# Schematic.net
KiCad netlist of a schematic drawn in Altium Designer
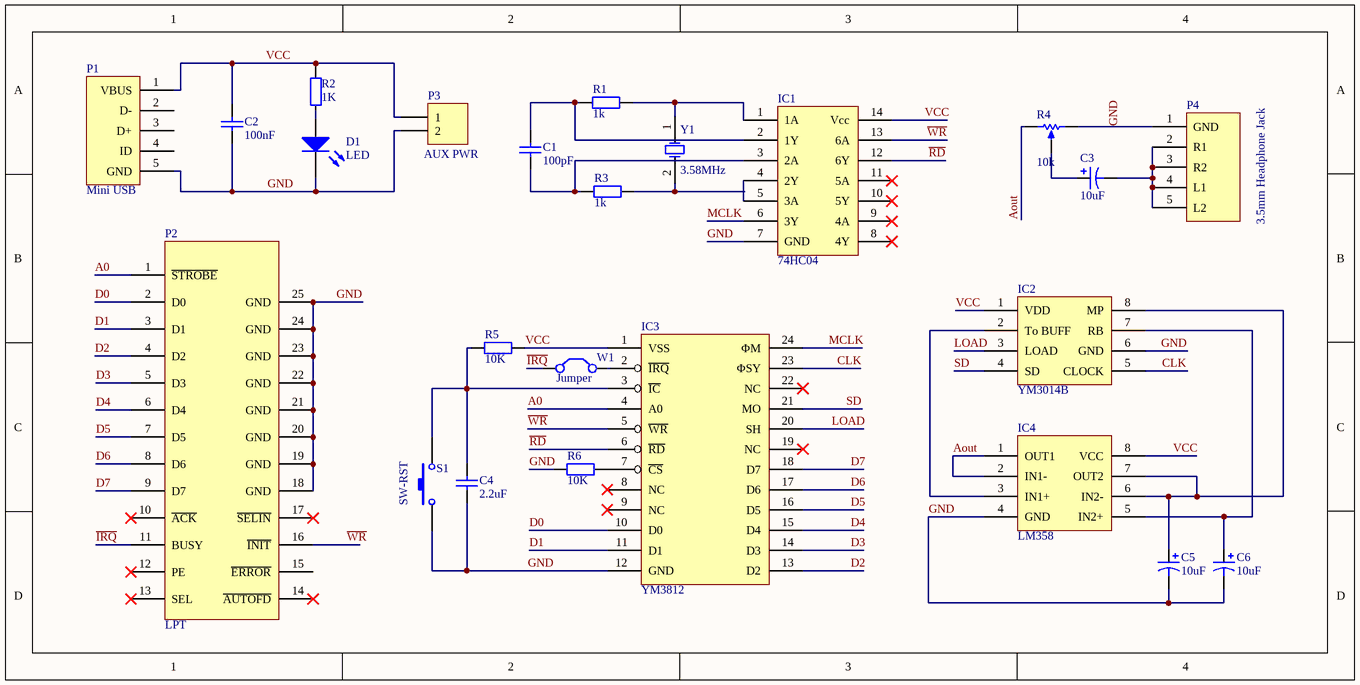
[diagram p0: Schematic.SchDoc]

(export (version "E")
  (design (tool "Eeschema 10.0.6"))
  (components
    (comp (ref "C1")
      (value "100pF")
      (footprint "MLCC")
      (description "Capacitor (Semiconductor SIM Model)")
      (libsource (lib "Miscellaneous Devices") (part "Cap Semi"))
    )
    (comp (ref "C2")
      (value "100nF")
      (footprint "MLCC")
      (description "Capacitor (Semiconductor SIM Model)")
      (libsource (lib "Miscellaneous Devices") (part "Cap Semi"))
    )
    (comp (ref "C3")
      (value "10uF")
      (footprint "CAP 2.0*5*11 - BK")
      (description "Polarized Capacitor (Surface Mount)")
      (libsource (lib "Miscellaneous Devices") (part "Cap Pol3"))
    )
    (comp (ref "C4")
      (value "2.2uF")
      (footprint "MLCC")
      (description "Capacitor (Semiconductor SIM Model)")
      (libsource (lib "Miscellaneous Devices") (part "Cap Semi"))
    )
    (comp (ref "C5")
      (value "10uF")
      (footprint "CAP 2.0*5*11 - BK")
      (description "Polarized Capacitor (Surface Mount)")
      (libsource (lib "Miscellaneous Devices") (part "Cap Pol3"))
    )
    (comp (ref "C6")
      (value "10uF")
      (footprint "CAP 2.0*5*11 - BK")
      (description "Polarized Capacitor (Surface Mount)")
      (libsource (lib "Miscellaneous Devices") (part "Cap Pol3"))
    )
    (comp (ref "D1")
      (value "LED")
      (footprint "LED 3MM-G")
      (description "Typical RED, GREEN, YELLOW, AMBER GaAs LED")
      (libsource (lib "Miscellaneous Devices") (part "LED2"))
    )
    (comp (ref "IC1") (value "74HC04") (footprint "DIP14-300_MH") (libsource (lib "Schlib") (part "7404")))
    (comp (ref "IC2") (value "YM3014B") (footprint "DIP8-300_MH") (libsource (lib "Schlib") (part "YM3014B")))
    (comp (ref "IC3") (value "YM3812") (footprint "DIP24-600_MH") (libsource (lib "Schlib") (part "YM3812")))
    (comp (ref "IC4") (value "LM358") (footprint "DIP8-300_MH") (libsource (lib "Schlib") (part "LM358")))
    (comp (ref "P1") (value "Mini USB") (libsource (lib "Schlib") (part "Mini USB")))
    (comp (ref "P2") (value "LPT") (footprint "DB25(DR252M)") (libsource (lib "Schlib") (part "LPT")))
    (comp (ref "P3")
      (value "AUX PWR")
      (footprint "HDR2.54-LI-2P")
      (description "Header, 2-Pin")
      (libsource (lib "Miscellaneous Connectors") (part "Header 2"))
    )
    (comp (ref "P4")
      (value "3.5mm Headphone Jack")
      (footprint "3F07_BK")
      (libsource (lib "Schlib") (part "3.5mm Headphone Jack"))
    )
    (comp (ref "R1")
      (value "1k")
      (footprint "RS 1/4W")
      (description "Resistor")
      (libsource (lib "Miscellaneous Devices") (part "Res2"))
    )
    (comp (ref "R2")
      (value "1K")
      (footprint "RS 1/4W")
      (description "Resistor")
      (libsource (lib "") (part "Res2_1"))
    )
    (comp (ref "R3")
      (value "1k")
      (footprint "RS 1/4W")
      (description "Resistor")
      (libsource (lib "Miscellaneous Devices") (part "Res2"))
    )
    (comp (ref "R4")
      (value "10k")
      (footprint "WH148-1-G15")
      (description "Potentiometer")
      (libsource (lib "Miscellaneous Devices") (part "RPot"))
    )
    (comp (ref "R5")
      (value "10K")
      (footprint "RS 1/4W")
      (description "Resistor")
      (libsource (lib "Miscellaneous Devices") (part "Res2"))
    )
    (comp (ref "R6")
      (value "10K")
      (footprint "RS 1/4W")
      (description "Resistor")
      (libsource (lib "Miscellaneous Devices") (part "Res2"))
    )
    (comp (ref "S1")
      (value "SW-RST")
      (footprint "TSW DIP-6*6*11")
      (description "Switch")
      (libsource (lib "Miscellaneous Devices") (part "SW-PB"))
    )
    (comp (ref "W1")
      (value "Jumper")
      (footprint "HDR2.54-LI-2P")
      (description "Jumper Wire")
      (libsource (lib "Miscellaneous Devices") (part "Jumper"))
    )
    (comp (ref "Y1")
      (value "3.58MHz")
      (footprint "OSC HC-49S")
      (description "Crystal Oscillator")
      (libsource (lib "Miscellaneous Devices") (part "XTAL"))
    )
  )
  (nets
    (net (code "1") (name "/A0") (class "Default")
      (node (ref "IC3") (pin "4") (pinfunction "A0_4") (pintype "passive"))
      (node (ref "P2") (pin "1") (pinfunction "~{STROBE}_1") (pintype "passive"))
    )
    (net (code "2") (name "/Aout") (class "Default")
      (node (ref "IC4") (pin "1") (pinfunction "OUT1_1") (pintype "passive"))
      (node (ref "IC4") (pin "2") (pinfunction "IN1-_2") (pintype "passive"))
      (node (ref "R4") (pin "1") (pinfunction "TOP_1") (pintype "passive"))
    )
    (net (code "3") (name "/CLK") (class "Default")
      (node (ref "IC2") (pin "5") (pinfunction "CLOCK_5") (pintype "passive"))
      (node (ref "IC3") (pin "23") (pinfunction "ΦSY_23") (pintype "passive"))
    )
    (net (code "4") (name "/D0") (class "Default")
      (node (ref "IC3") (pin "10") (pinfunction "D0_10") (pintype "passive"))
      (node (ref "P2") (pin "2") (pinfunction "D0_2") (pintype "passive"))
    )
    (net (code "5") (name "/D1") (class "Default")
      (node (ref "IC3") (pin "11") (pinfunction "D1_11") (pintype "passive"))
      (node (ref "P2") (pin "3") (pinfunction "D1_3") (pintype "passive"))
    )
    (net (code "6") (name "/D2") (class "Default")
      (node (ref "IC3") (pin "13") (pinfunction "D2_13") (pintype "passive"))
      (node (ref "P2") (pin "4") (pinfunction "D2_4") (pintype "passive"))
    )
    (net (code "7") (name "/D3") (class "Default")
      (node (ref "IC3") (pin "14") (pinfunction "D3_14") (pintype "passive"))
      (node (ref "P2") (pin "5") (pinfunction "D3_5") (pintype "passive"))
    )
    (net (code "8") (name "/D4") (class "Default")
      (node (ref "IC3") (pin "15") (pinfunction "D4_15") (pintype "passive"))
      (node (ref "P2") (pin "6") (pinfunction "D4_6") (pintype "passive"))
    )
    (net (code "9") (name "/D5") (class "Default")
      (node (ref "IC3") (pin "16") (pinfunction "D5_16") (pintype "passive"))
      (node (ref "P2") (pin "7") (pinfunction "D5_7") (pintype "passive"))
    )
    (net (code "10") (name "/D6") (class "Default")
      (node (ref "IC3") (pin "17") (pinfunction "D6_17") (pintype "passive"))
      (node (ref "P2") (pin "8") (pinfunction "D6_8") (pintype "passive"))
    )
    (net (code "11") (name "/D7") (class "Default")
      (node (ref "IC3") (pin "18") (pinfunction "D7_18") (pintype "passive"))
      (node (ref "P2") (pin "9") (pinfunction "D7_9") (pintype "passive"))
    )
    (net (code "12") (name "/GND") (class "Default")
      (node (ref "C2") (pin "1") (pinfunction "1_1") (pintype "passive"))
      (node (ref "C4") (pin "1") (pinfunction "1_1") (pintype "passive"))
      (node (ref "C5") (pin "2") (pinfunction "2_2") (pintype "passive"))
      (node (ref "C6") (pin "2") (pinfunction "2_2") (pintype "passive"))
      (node (ref "D1") (pin "2") (pinfunction "K_2") (pintype "passive"))
      (node (ref "IC1") (pin "7") (pinfunction "GND_7") (pintype "passive"))
      (node (ref "IC2") (pin "6") (pinfunction "GND_6") (pintype "passive"))
      (node (ref "IC3") (pin "12") (pinfunction "GND_12") (pintype "passive"))
      (node (ref "IC4") (pin "4") (pinfunction "GND_4") (pintype "passive"))
      (node (ref "P1") (pin "5") (pinfunction "GND_5") (pintype "passive"))
      (node (ref "P2") (pin "18") (pinfunction "GND_18") (pintype "passive"))
      (node (ref "P2") (pin "19") (pinfunction "GND_19") (pintype "passive"))
      (node (ref "P2") (pin "20") (pinfunction "GND_20") (pintype "passive"))
      (node (ref "P2") (pin "21") (pinfunction "GND_21") (pintype "passive"))
      (node (ref "P2") (pin "22") (pinfunction "GND_22") (pintype "passive"))
      (node (ref "P2") (pin "23") (pinfunction "GND_23") (pintype "passive"))
      (node (ref "P2") (pin "24") (pinfunction "GND_24") (pintype "passive"))
      (node (ref "P2") (pin "25") (pinfunction "GND_25") (pintype "passive"))
      (node (ref "P3") (pin "2") (pinfunction "2_2") (pintype "passive"))
      (node (ref "P4") (pin "1") (pinfunction "GND_1") (pintype "passive"))
      (node (ref "R4") (pin "2") (pinfunction "BOT_2") (pintype "passive"))
      (node (ref "R6") (pin "1") (pinfunction "1_1") (pintype "passive"))
      (node (ref "S1") (pin "1") (pinfunction "1_1") (pintype "passive"))
    )
    (net (code "13") (name "/LOAD") (class "Default")
      (node (ref "IC2") (pin "3") (pinfunction "LOAD_3") (pintype "passive"))
      (node (ref "IC3") (pin "20") (pinfunction "SH_20") (pintype "passive"))
    )
    (net (code "14") (name "/MCLK") (class "Default")
      (node (ref "IC1") (pin "6") (pinfunction "3Y_6") (pintype "passive"))
      (node (ref "IC3") (pin "24") (pinfunction "ΦM_24") (pintype "passive"))
    )
    (net (code "15") (name "/SD") (class "Default")
      (node (ref "IC2") (pin "4") (pinfunction "SD_4") (pintype "passive"))
      (node (ref "IC3") (pin "21") (pinfunction "MO_21") (pintype "passive"))
    )
    (net (code "16") (name "/VCC") (class "Default")
      (node (ref "C2") (pin "2") (pinfunction "2_2") (pintype "passive"))
      (node (ref "IC1") (pin "14") (pinfunction "Vcc_14") (pintype "passive"))
      (node (ref "IC2") (pin "1") (pinfunction "VDD_1") (pintype "passive"))
      (node (ref "IC3") (pin "1") (pinfunction "VSS_1") (pintype "passive"))
      (node (ref "IC4") (pin "8") (pinfunction "VCC_8") (pintype "passive"))
      (node (ref "P1") (pin "1") (pinfunction "VBUS_1") (pintype "passive"))
      (node (ref "P3") (pin "1") (pinfunction "1_1") (pintype "passive"))
      (node (ref "R2") (pin "2") (pinfunction "2_2") (pintype "passive"))
      (node (ref "R5") (pin "2") (pinfunction "2_2") (pintype "passive"))
    )
    (net (code "17") (name "/~{IRQ}") (class "Default")
      (node (ref "P2") (pin "11") (pinfunction "BUSY_11") (pintype "passive"))
      (node (ref "W1") (pin "1") (pinfunction "C1_1") (pintype "passive"))
    )
    (net (code "18") (name "/~{RD}") (class "Default")
      (node (ref "IC1") (pin "12") (pinfunction "6Y_12") (pintype "passive"))
      (node (ref "IC3") (pin "6") (pinfunction "~{RD}_6") (pintype "passive"))
    )
    (net (code "19") (name "/~{WR}") (class "Default")
      (node (ref "IC1") (pin "13") (pinfunction "6A_13") (pintype "passive"))
      (node (ref "IC3") (pin "5") (pinfunction "~{WR}_5") (pintype "passive"))
      (node (ref "P2") (pin "16") (pinfunction "~{INIT}_16") (pintype "passive"))
    )
    (net (code "20") (name "Net-(D1-A)") (class "Default")
      (node (ref "D1") (pin "1") (pinfunction "A_1") (pintype "passive"))
      (node (ref "R2") (pin "1") (pinfunction "1_1") (pintype "passive"))
    )
    (net (code "21") (name "Net-(IC1-1A)") (class "Default")
      (node (ref "IC1") (pin "1") (pinfunction "1A_1") (pintype "passive"))
      (node (ref "R1") (pin "2") (pinfunction "2_2") (pintype "passive"))
      (node (ref "Y1") (pin "1") (pinfunction "OSC1_1") (pintype "passive"))
    )
    (net (code "22") (name "Net-(IC1-1Y)") (class "Default")
      (node (ref "C1") (pin "2") (pinfunction "2_2") (pintype "passive"))
      (node (ref "IC1") (pin "2") (pinfunction "1Y_2") (pintype "passive"))
      (node (ref "R1") (pin "1") (pinfunction "1_1") (pintype "passive"))
    )
    (net (code "23") (name "Net-(IC1-2A)") (class "Default")
      (node (ref "C1") (pin "1") (pinfunction "1_1") (pintype "passive"))
      (node (ref "IC1") (pin "3") (pinfunction "2A_3") (pintype "passive"))
      (node (ref "R3") (pin "1") (pinfunction "1_1") (pintype "passive"))
    )
    (net (code "24") (name "Net-(IC1-2Y)") (class "Default")
      (node (ref "IC1") (pin "4") (pinfunction "2Y_4") (pintype "passive"))
      (node (ref "IC1") (pin "5") (pinfunction "3A_5") (pintype "passive"))
    )
    (net (code "25") (name "Net-(IC2-MP)") (class "Default")
      (node (ref "C5") (pin "1") (pinfunction "1_1") (pintype "passive"))
      (node (ref "IC2") (pin "8") (pinfunction "MP_8") (pintype "passive"))
      (node (ref "IC4") (pin "6") (pinfunction "IN2-_6") (pintype "passive"))
      (node (ref "IC4") (pin "7") (pinfunction "OUT2_7") (pintype "passive"))
    )
    (net (code "26") (name "Net-(IC2-RB)") (class "Default")
      (node (ref "C6") (pin "1") (pinfunction "1_1") (pintype "passive"))
      (node (ref "IC2") (pin "7") (pinfunction "RB_7") (pintype "passive"))
      (node (ref "IC4") (pin "5") (pinfunction "IN2+_5") (pintype "passive"))
    )
    (net (code "27") (name "Net-(IC2-To_BUFF)") (class "Default")
      (node (ref "IC2") (pin "2") (pinfunction "To_BUFF_2") (pintype "passive"))
      (node (ref "IC4") (pin "3") (pinfunction "IN1+_3") (pintype "passive"))
    )
    (net (code "28") (name "Net-(IC3-~{CS})") (class "Default")
      (node (ref "IC3") (pin "7") (pinfunction "~{CS}_7") (pintype "passive"))
      (node (ref "R6") (pin "2") (pinfunction "2_2") (pintype "passive"))
    )
    (net (code "29") (name "Net-(IC3-~{IC})") (class "Default")
      (node (ref "C4") (pin "2") (pinfunction "2_2") (pintype "passive"))
      (node (ref "IC3") (pin "3") (pinfunction "~{IC}_3") (pintype "passive"))
      (node (ref "R5") (pin "1") (pinfunction "1_1") (pintype "passive"))
      (node (ref "S1") (pin "2") (pinfunction "2_2") (pintype "passive"))
    )
    (net (code "30") (name "Net-(IC3-~{IRQ})") (class "Default")
      (node (ref "IC3") (pin "2") (pinfunction "~{IRQ}_2") (pintype "passive"))
      (node (ref "W1") (pin "2") (pinfunction "C2_2") (pintype "passive"))
    )
    (net (code "31") (name "Net-(P4-L1)") (class "Default")
      (node (ref "C3") (pin "2") (pinfunction "2_2") (pintype "passive"))
      (node (ref "P4") (pin "2") (pinfunction "R1_2") (pintype "passive"))
      (node (ref "P4") (pin "3") (pinfunction "R2_3") (pintype "passive"))
      (node (ref "P4") (pin "4") (pinfunction "L1_4") (pintype "passive"))
      (node (ref "P4") (pin "5") (pinfunction "L2_5") (pintype "passive"))
    )
    (net (code "32") (name "Net-(R4-TAP)") (class "Default")
      (node (ref "C3") (pin "1") (pinfunction "1_1") (pintype "passive"))
      (node (ref "R4") (pin "3") (pinfunction "TAP_3") (pintype "passive"))
    )
    (net (code "33") (name "Net-(Y1-OSC2)") (class "Default")
      (node (ref "R3") (pin "2") (pinfunction "2_2") (pintype "passive"))
      (node (ref "Y1") (pin "2") (pinfunction "OSC2_2") (pintype "passive"))
    )
    (net (code "34") (name "unconnected-(IC1-4A-Pad9)") (class "Default")
      (node (ref "IC1") (pin "9") (pinfunction "4A_9") (pintype "passive+no_connect"))
    )
    (net (code "35") (name "unconnected-(IC1-4Y-Pad8)") (class "Default")
      (node (ref "IC1") (pin "8") (pinfunction "4Y_8") (pintype "passive+no_connect"))
    )
    (net (code "36") (name "unconnected-(IC1-5A-Pad11)") (class "Default")
      (node (ref "IC1") (pin "11") (pinfunction "5A_11") (pintype "passive+no_connect"))
    )
    (net (code "37") (name "unconnected-(IC1-5Y-Pad10)") (class "Default")
      (node (ref "IC1") (pin "10") (pinfunction "5Y_10") (pintype "passive+no_connect"))
    )
    (net (code "38") (name "unconnected-(IC3-NC-Pad8)") (class "Default")
      (node (ref "IC3") (pin "8") (pinfunction "NC_8") (pintype "passive+no_connect"))
    )
    (net (code "39") (name "unconnected-(IC3-NC-Pad9)") (class "Default")
      (node (ref "IC3") (pin "9") (pinfunction "NC_9") (pintype "passive+no_connect"))
    )
    (net (code "40") (name "unconnected-(IC3-NC-Pad19)") (class "Default")
      (node (ref "IC3") (pin "19") (pinfunction "NC_19") (pintype "passive+no_connect"))
    )
    (net (code "41") (name "unconnected-(IC3-NC-Pad22)") (class "Default")
      (node (ref "IC3") (pin "22") (pinfunction "NC_22") (pintype "passive+no_connect"))
    )
    (net (code "42") (name "unconnected-(P1-D+-Pad3)") (class "Default")
      (node (ref "P1") (pin "3") (pinfunction "D+_3") (pintype "passive"))
    )
    (net (code "43") (name "unconnected-(P1-D--Pad2)") (class "Default")
      (node (ref "P1") (pin "2") (pinfunction "D-_2") (pintype "passive"))
    )
    (net (code "44") (name "unconnected-(P1-ID-Pad4)") (class "Default")
      (node (ref "P1") (pin "4") (pinfunction "ID_4") (pintype "passive"))
    )
    (net (code "45") (name "unconnected-(P2-PE-Pad12)") (class "Default")
      (node (ref "P2") (pin "12") (pinfunction "PE_12") (pintype "passive+no_connect"))
    )
    (net (code "46") (name "unconnected-(P2-SEL-Pad13)") (class "Default")
      (node (ref "P2") (pin "13") (pinfunction "SEL_13") (pintype "passive+no_connect"))
    )
    (net (code "47") (name "unconnected-(P2-~{ACK}-Pad10)") (class "Default")
      (node (ref "P2") (pin "10") (pinfunction "~{ACK}_10") (pintype "passive+no_connect"))
    )
    (net (code "48") (name "unconnected-(P2-~{AUTOFD}-Pad14)") (class "Default")
      (node (ref "P2") (pin "14") (pinfunction "~{AUTOFD}_14") (pintype "passive+no_connect"))
    )
    (net (code "49") (name "unconnected-(P2-~{ERROR}-Pad15)") (class "Default")
      (node (ref "P2") (pin "15") (pinfunction "~{ERROR}_15") (pintype "passive"))
    )
    (net (code "50") (name "unconnected-(P2-~{SELIN}-Pad17)") (class "Default")
      (node (ref "P2") (pin "17") (pinfunction "~{SELIN}_17") (pintype "passive+no_connect"))
    )
  )
)
